# FPGA_R.net
KiCad netlist of a schematic drawn in Altium Designer
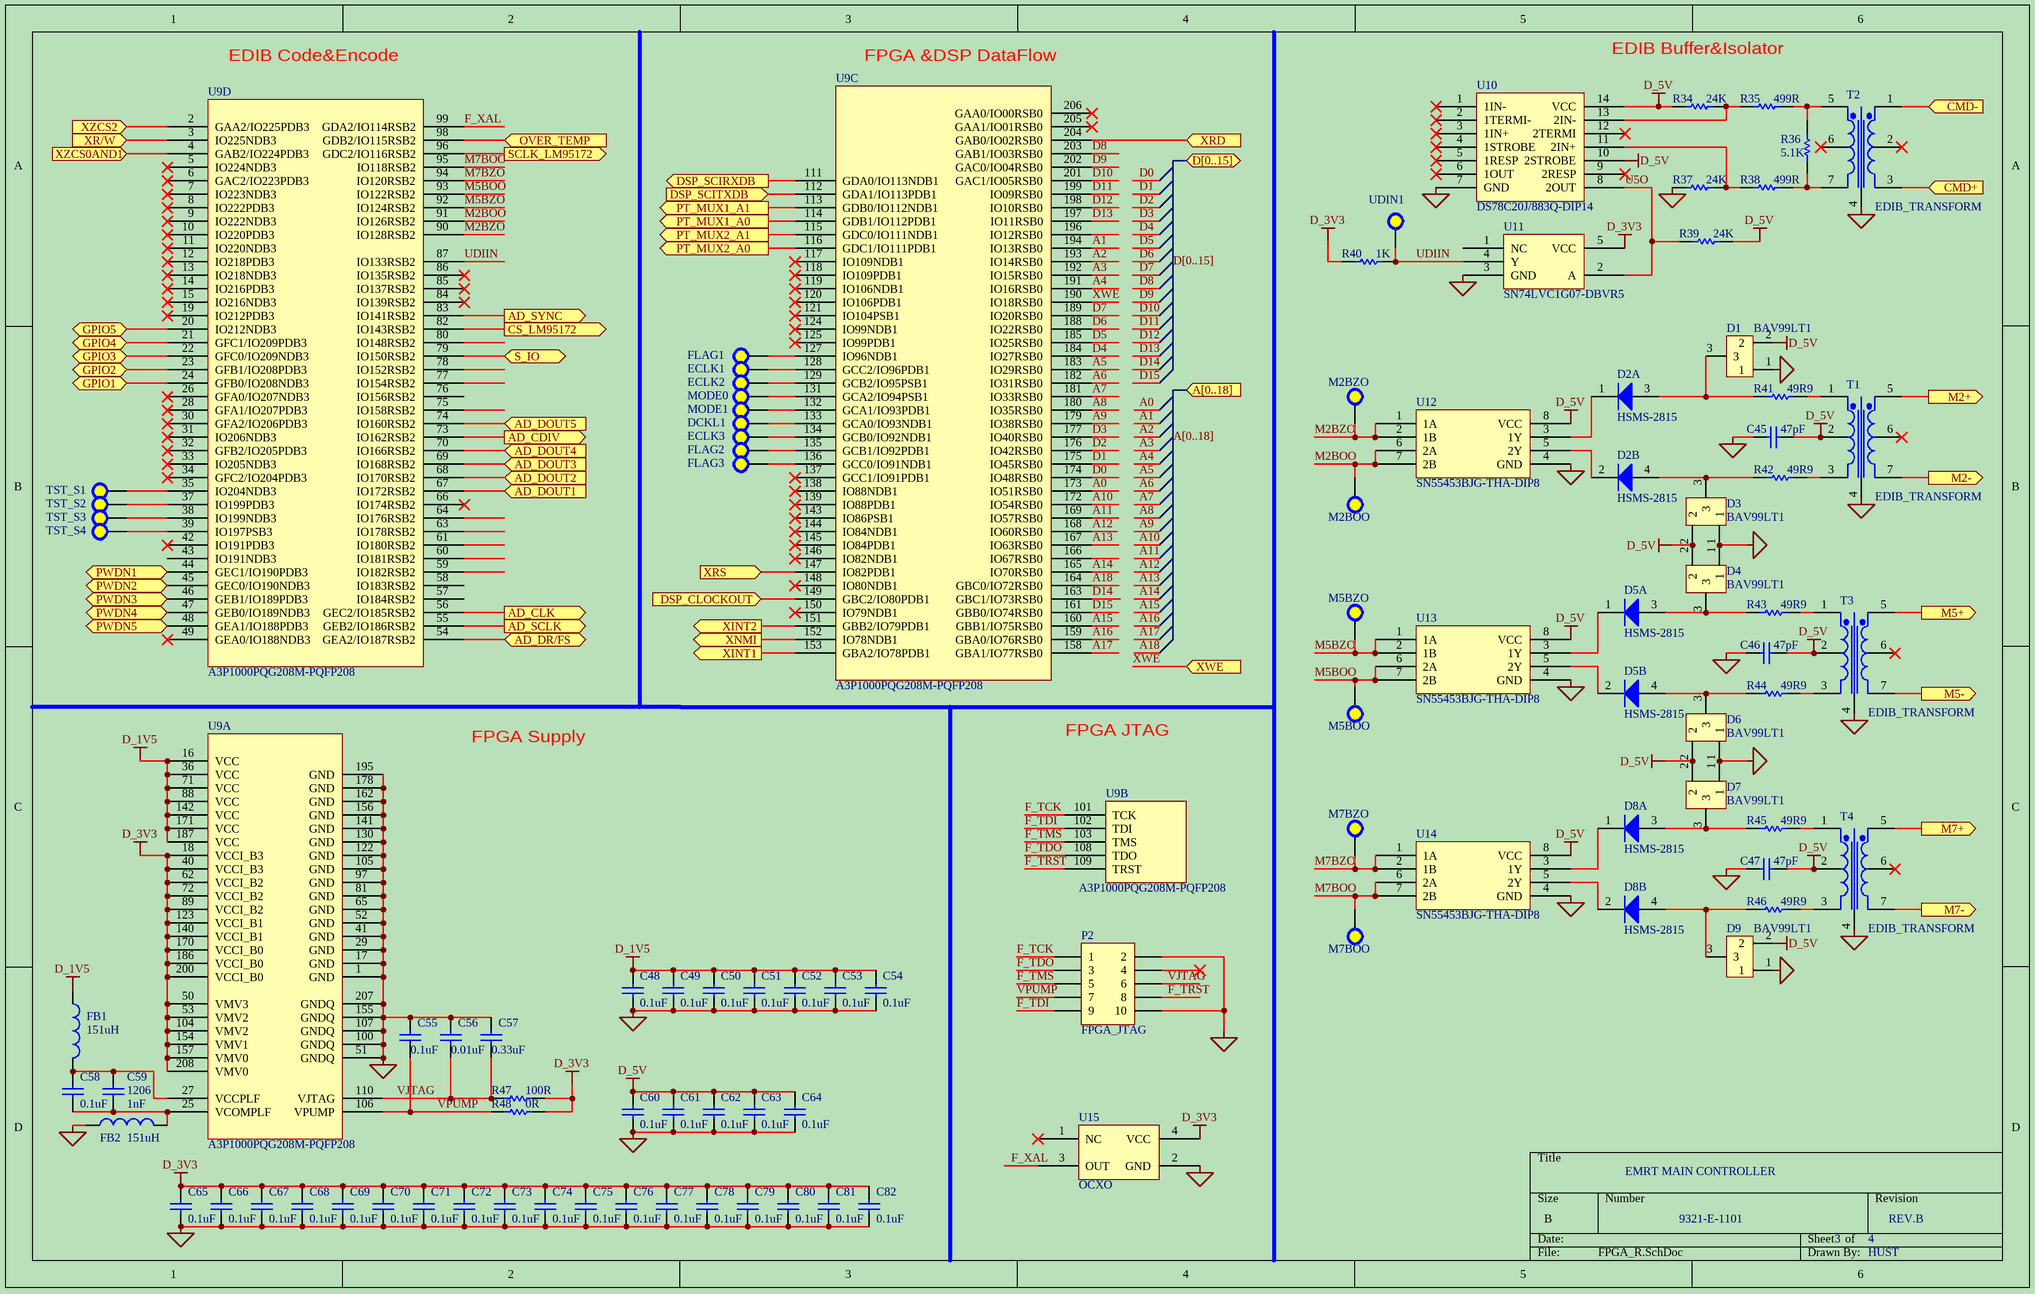
[diagram p0: FPGA_R.SchDoc]

(export (version "E")
  (design (tool "Eeschema 10.0.6"))
  (components
    (comp (ref "C45")
      (value "47pF")
      (footprint "CAPS0805_57")
      (description "Capacitor")
      (fields (field (name "PART NUMBER") "Y20025084") (field (name "Comment") "Cap"))
      (libsource (lib "Cap") (part "Cap"))
    )
    (comp (ref "C46")
      (value "47pF")
      (footprint "CAPS0805_57")
      (description "Capacitor")
      (fields (field (name "PART NUMBER") "Y20025084") (field (name "Comment") "Cap"))
      (libsource (lib "Cap") (part "Cap"))
    )
    (comp (ref "C47")
      (value "47pF")
      (footprint "CAPS0805_57")
      (description "Capacitor")
      (fields (field (name "PART NUMBER") "Y20025084") (field (name "Comment") "Cap"))
      (libsource (lib "Cap") (part "Cap"))
    )
    (comp (ref "C48")
      (value "0.1uF")
      (footprint "CAPS0805_57")
      (description "Capacitor")
      (fields (field (name "PART NUMBER") "Y20025084") (field (name "Comment") "Cap"))
      (libsource (lib "Cap") (part "Cap"))
    )
    (comp (ref "C49")
      (value "0.1uF")
      (footprint "CAPS0805_57")
      (description "Capacitor")
      (fields (field (name "PART NUMBER") "Y20025084") (field (name "Comment") "Cap"))
      (libsource (lib "Cap") (part "Cap"))
    )
    (comp (ref "C50")
      (value "0.1uF")
      (footprint "CAPS0805_57")
      (description "Capacitor")
      (fields (field (name "PART NUMBER") "Y20025084") (field (name "Comment") "Cap"))
      (libsource (lib "Cap") (part "Cap"))
    )
    (comp (ref "C51")
      (value "0.1uF")
      (footprint "CAPS0805_57")
      (description "Capacitor")
      (fields (field (name "PART NUMBER") "Y20025084") (field (name "Comment") "Cap"))
      (libsource (lib "Cap") (part "Cap"))
    )
    (comp (ref "C52")
      (value "0.1uF")
      (footprint "CAPS0805_57")
      (description "Capacitor")
      (fields (field (name "PART NUMBER") "Y20025084") (field (name "Comment") "Cap"))
      (libsource (lib "Cap") (part "Cap"))
    )
    (comp (ref "C53")
      (value "0.1uF")
      (footprint "CAPS0805_57")
      (description "Capacitor")
      (fields (field (name "PART NUMBER") "Y20025084") (field (name "Comment") "Cap"))
      (libsource (lib "Cap") (part "Cap"))
    )
    (comp (ref "C54")
      (value "0.1uF")
      (footprint "CAPS0805_57")
      (description "Capacitor")
      (fields (field (name "PART NUMBER") "Y20025084") (field (name "Comment") "Cap"))
      (libsource (lib "Cap") (part "Cap"))
    )
    (comp (ref "C55")
      (value "0.1uF")
      (footprint "CAPS0805_57")
      (description "Capacitor")
      (fields (field (name "PART NUMBER") "Y20025084") (field (name "Comment") "Cap"))
      (libsource (lib "Cap") (part "Cap"))
    )
    (comp (ref "C56")
      (value "0.01uF")
      (footprint "CAPS0805_57")
      (description "Capacitor")
      (fields (field (name "PART NUMBER") "Y20025084") (field (name "Comment") "Cap"))
      (libsource (lib "Cap") (part "Cap"))
    )
    (comp (ref "C57")
      (value "0.33uF")
      (footprint "CAPS0805_57")
      (description "Capacitor")
      (fields (field (name "PART NUMBER") "Y20025084") (field (name "Comment") "Cap"))
      (libsource (lib "Cap") (part "Cap"))
    )
    (comp (ref "C58")
      (value "0.1uF")
      (footprint "CAPS0805_57")
      (description "Capacitor")
      (fields (field (name "PART NUMBER") "Y20025084") (field (name "Comment") "Cap"))
      (libsource (lib "Cap") (part "Cap"))
    )
    (comp (ref "C59")
      (value "1206")
      (footprint "CAPS1206_43")
      (description "Capacitor")
      (fields (field (name "ALTIUM_VALUE") "1nF") (field (name "PART NUMBER") "Y20024113"))
      (libsource (lib "Cap") (part "Cap"))
    )
    (comp (ref "C60")
      (value "0.1uF")
      (footprint "CAPS0805_57")
      (description "Capacitor")
      (fields (field (name "PART NUMBER") "Y20025084") (field (name "Comment") "Cap"))
      (libsource (lib "Cap") (part "Cap"))
    )
    (comp (ref "C61")
      (value "0.1uF")
      (footprint "CAPS0805_57")
      (description "Capacitor")
      (fields (field (name "PART NUMBER") "Y20025084") (field (name "Comment") "Cap"))
      (libsource (lib "Cap") (part "Cap"))
    )
    (comp (ref "C62")
      (value "0.1uF")
      (footprint "CAPS0805_57")
      (description "Capacitor")
      (fields (field (name "PART NUMBER") "Y20025084") (field (name "Comment") "Cap"))
      (libsource (lib "Cap") (part "Cap"))
    )
    (comp (ref "C63")
      (value "0.1uF")
      (footprint "CAPS0805_57")
      (description "Capacitor")
      (fields (field (name "PART NUMBER") "Y20025084") (field (name "Comment") "Cap"))
      (libsource (lib "Cap") (part "Cap"))
    )
    (comp (ref "C64")
      (value "0.1uF")
      (footprint "CAPS0805_57")
      (description "Capacitor")
      (fields (field (name "PART NUMBER") "Y20025084") (field (name "Comment") "Cap"))
      (libsource (lib "Cap") (part "Cap"))
    )
    (comp (ref "C65")
      (value "0.1uF")
      (footprint "CAPS0805_57")
      (description "Capacitor")
      (fields (field (name "PART NUMBER") "Y20025084") (field (name "Comment") "Cap"))
      (libsource (lib "Cap") (part "Cap"))
    )
    (comp (ref "C66")
      (value "0.1uF")
      (footprint "CAPS0805_57")
      (description "Capacitor")
      (fields (field (name "PART NUMBER") "Y20025084") (field (name "Comment") "Cap"))
      (libsource (lib "Cap") (part "Cap"))
    )
    (comp (ref "C67")
      (value "0.1uF")
      (footprint "CAPS0805_57")
      (description "Capacitor")
      (fields (field (name "PART NUMBER") "Y20025084") (field (name "Comment") "Cap"))
      (libsource (lib "Cap") (part "Cap"))
    )
    (comp (ref "C68")
      (value "0.1uF")
      (footprint "CAPS0805_57")
      (description "Capacitor")
      (fields (field (name "PART NUMBER") "Y20025084") (field (name "Comment") "Cap"))
      (libsource (lib "Cap") (part "Cap"))
    )
    (comp (ref "C69")
      (value "0.1uF")
      (footprint "CAPS0805_57")
      (description "Capacitor")
      (fields (field (name "PART NUMBER") "Y20025084") (field (name "Comment") "Cap"))
      (libsource (lib "Cap") (part "Cap"))
    )
    (comp (ref "C70")
      (value "0.1uF")
      (footprint "CAPS0805_57")
      (description "Capacitor")
      (fields (field (name "PART NUMBER") "Y20025084") (field (name "Comment") "Cap"))
      (libsource (lib "Cap") (part "Cap"))
    )
    (comp (ref "C71")
      (value "0.1uF")
      (footprint "CAPS0805_57")
      (description "Capacitor")
      (fields (field (name "PART NUMBER") "Y20025084") (field (name "Comment") "Cap"))
      (libsource (lib "Cap") (part "Cap"))
    )
    (comp (ref "C72")
      (value "0.1uF")
      (footprint "CAPS0805_57")
      (description "Capacitor")
      (fields (field (name "PART NUMBER") "Y20025084") (field (name "Comment") "Cap"))
      (libsource (lib "Cap") (part "Cap"))
    )
    (comp (ref "C73")
      (value "0.1uF")
      (footprint "CAPS0805_57")
      (description "Capacitor")
      (fields (field (name "PART NUMBER") "Y20025084") (field (name "Comment") "Cap"))
      (libsource (lib "Cap") (part "Cap"))
    )
    (comp (ref "C74")
      (value "0.1uF")
      (footprint "CAPS0805_57")
      (description "Capacitor")
      (fields (field (name "PART NUMBER") "Y20025084") (field (name "Comment") "Cap"))
      (libsource (lib "Cap") (part "Cap"))
    )
    (comp (ref "C75")
      (value "0.1uF")
      (footprint "CAPS0805_57")
      (description "Capacitor")
      (fields (field (name "PART NUMBER") "Y20025084") (field (name "Comment") "Cap"))
      (libsource (lib "Cap") (part "Cap"))
    )
    (comp (ref "C76")
      (value "0.1uF")
      (footprint "CAPS0805_57")
      (description "Capacitor")
      (fields (field (name "PART NUMBER") "Y20025084") (field (name "Comment") "Cap"))
      (libsource (lib "Cap") (part "Cap"))
    )
    (comp (ref "C77")
      (value "0.1uF")
      (footprint "CAPS0805_57")
      (description "Capacitor")
      (fields (field (name "PART NUMBER") "Y20025084") (field (name "Comment") "Cap"))
      (libsource (lib "Cap") (part "Cap"))
    )
    (comp (ref "C78")
      (value "0.1uF")
      (footprint "CAPS0805_57")
      (description "Capacitor")
      (fields (field (name "PART NUMBER") "Y20025084") (field (name "Comment") "Cap"))
      (libsource (lib "Cap") (part "Cap"))
    )
    (comp (ref "C79")
      (value "0.1uF")
      (footprint "CAPS0805_57")
      (description "Capacitor")
      (fields (field (name "PART NUMBER") "Y20025084") (field (name "Comment") "Cap"))
      (libsource (lib "Cap") (part "Cap"))
    )
    (comp (ref "C80")
      (value "0.1uF")
      (footprint "CAPS0805_57")
      (description "Capacitor")
      (fields (field (name "PART NUMBER") "Y20025084") (field (name "Comment") "Cap"))
      (libsource (lib "Cap") (part "Cap"))
    )
    (comp (ref "C81")
      (value "0.1uF")
      (footprint "CAPS0805_57")
      (description "Capacitor")
      (fields (field (name "PART NUMBER") "Y20025084") (field (name "Comment") "Cap"))
      (libsource (lib "Cap") (part "Cap"))
    )
    (comp (ref "C82")
      (value "0.1uF")
      (footprint "CAPS0805_57")
      (description "Capacitor")
      (fields (field (name "PART NUMBER") "Y20025084") (field (name "Comment") "Cap"))
      (libsource (lib "Cap") (part "Cap"))
    )
    (comp (ref "D1")
      (value "BAV99LT1")
      (footprint "T-PDSO_3q290×240×111_p95")
      (libsource (lib "") (part "BAV99LT1_1"))
    )
    (comp (ref "D2")
      (value "HSMS-2815")
      (footprint "T-PDSO_4q290×240×110_p190")
      (libsource (lib "srj") (part "HSMS-2815"))
    )
    (comp (ref "D3")
      (value "BAV99LT1")
      (footprint "T-PDSO_3q290×240×111_p95")
      (libsource (lib "") (part "BAV99LT1_2"))
    )
    (comp (ref "D4")
      (value "BAV99LT1")
      (footprint "T-PDSO_3q290×240×111_p95")
      (libsource (lib "srj") (part "BAV99LT1"))
    )
    (comp (ref "D5")
      (value "HSMS-2815")
      (footprint "T-PDSO_4q290×240×110_p190")
      (libsource (lib "srj") (part "HSMS-2815"))
    )
    (comp (ref "D6")
      (value "BAV99LT1")
      (footprint "T-PDSO_3q290×240×111_p95")
      (libsource (lib "") (part "BAV99LT1_2"))
    )
    (comp (ref "D7")
      (value "BAV99LT1")
      (footprint "T-PDSO_3q290×240×111_p95")
      (libsource (lib "srj") (part "BAV99LT1"))
    )
    (comp (ref "D8")
      (value "HSMS-2815")
      (footprint "T-PDSO_4q290×240×110_p190")
      (libsource (lib "srj") (part "HSMS-2815"))
    )
    (comp (ref "D9")
      (value "BAV99LT1")
      (footprint "T-PDSO_3q290×240×111_p95")
      (libsource (lib "") (part "BAV99LT1_1"))
    )
    (comp (ref "DCKL1")
      (value "TEST_SMALL")
      (footprint "test_small")
      (libsource (lib "srj") (part "TEST_SMALL"))
    )
    (comp (ref "ECLK1")
      (value "TEST_SMALL")
      (footprint "test_small")
      (libsource (lib "srj") (part "TEST_SMALL"))
    )
    (comp (ref "ECLK2")
      (value "TEST_SMALL")
      (footprint "test_small")
      (libsource (lib "srj") (part "TEST_SMALL"))
    )
    (comp (ref "ECLK3")
      (value "TEST_SMALL")
      (footprint "test_small")
      (libsource (lib "srj") (part "TEST_SMALL"))
    )
    (comp (ref "FB1")
      (value "151uH")
      (footprint "inductor_1008")
      (description "Inductor")
      (fields
        (field (name "MANUFACTURER") "Generic Components")
        (field (name "PUBLISHER") "Altium Hobart Technology Centre")
      )
      (libsource (lib "Miscellaneous Devices") (part "Inductor"))
    )
    (comp (ref "FB2")
      (value "151uH")
      (footprint "inductor_1008")
      (description "Inductor")
      (fields
        (field (name "MANUFACTURER") "Generic Components")
        (field (name "PUBLISHER") "Altium Hobart Technology Centre")
      )
      (libsource (lib "Miscellaneous Devices") (part "Inductor"))
    )
    (comp (ref "FLAG1")
      (value "TEST_SMALL")
      (footprint "test_small")
      (libsource (lib "srj") (part "TEST_SMALL"))
    )
    (comp (ref "FLAG2")
      (value "TEST_SMALL")
      (footprint "test_small")
      (libsource (lib "srj") (part "TEST_SMALL"))
    )
    (comp (ref "FLAG3")
      (value "TEST_SMALL")
      (footprint "test_small")
      (libsource (lib "srj") (part "TEST_SMALL"))
    )
    (comp (ref "M2BOO")
      (value "TEST_SMALL")
      (footprint "test_small")
      (libsource (lib "srj") (part "TEST_SMALL"))
    )
    (comp (ref "M2BZO")
      (value "TEST_SMALL")
      (footprint "test_small")
      (libsource (lib "srj") (part "TEST_SMALL"))
    )
    (comp (ref "M5BOO")
      (value "TEST_SMALL")
      (footprint "test_small")
      (libsource (lib "srj") (part "TEST_SMALL"))
    )
    (comp (ref "M5BZO")
      (value "TEST_SMALL")
      (footprint "test_small")
      (libsource (lib "srj") (part "TEST_SMALL"))
    )
    (comp (ref "M7BOO")
      (value "TEST_SMALL")
      (footprint "test_small")
      (libsource (lib "srj") (part "TEST_SMALL"))
    )
    (comp (ref "M7BZO")
      (value "TEST_SMALL")
      (footprint "test_small")
      (libsource (lib "srj") (part "TEST_SMALL"))
    )
    (comp (ref "MODE0")
      (value "TEST_SMALL")
      (footprint "test_small")
      (libsource (lib "srj") (part "TEST_SMALL"))
    )
    (comp (ref "MODE1")
      (value "TEST_SMALL")
      (footprint "test_small")
      (libsource (lib "srj") (part "TEST_SMALL"))
    )
    (comp (ref "P2")
      (value "FPGA_JTAG")
      (footprint "HDR2X5")
      (description "Header, 5-Pin, Dual row")
      (fields (field (name "PUBLISHER") "Altium Limited"))
      (libsource (lib "Miscellaneous Connectors") (part "Header 5X2"))
    )
    (comp (ref "R34")
      (value "24K")
      (footprint "RESS0805")
      (description "Semiconductor Resistor")
      (fields
        (field (name "MANUFACTURER") "Generic Components")
        (field (name "Comment") "Res")
        (field (name "PUBLISHER") "Altium Hobart Technology Centre")
      )
      (libsource (lib "EMRT MAIN CONTROLLER") (part "Res"))
    )
    (comp (ref "R35")
      (value "499R")
      (footprint "RESS0805")
      (description "Semiconductor Resistor")
      (fields
        (field (name "MANUFACTURER") "Generic Components")
        (field (name "Comment") "Res")
        (field (name "PUBLISHER") "Altium Hobart Technology Centre")
      )
      (libsource (lib "EMRT MAIN CONTROLLER") (part "Res"))
    )
    (comp (ref "R36")
      (value "5.1K")
      (footprint "RESS0805")
      (description "Semiconductor Resistor")
      (fields
        (field (name "MANUFACTURER") "Generic Components")
        (field (name "Comment") "Res")
        (field (name "PUBLISHER") "Altium Hobart Technology Centre")
      )
      (libsource (lib "EMRT MAIN CONTROLLER") (part "Res"))
    )
    (comp (ref "R37")
      (value "24K")
      (footprint "RESS0805")
      (description "Semiconductor Resistor")
      (fields
        (field (name "MANUFACTURER") "Generic Components")
        (field (name "Comment") "Res")
        (field (name "PUBLISHER") "Altium Hobart Technology Centre")
      )
      (libsource (lib "EMRT MAIN CONTROLLER") (part "Res"))
    )
    (comp (ref "R38")
      (value "499R")
      (footprint "RESS0805")
      (description "Semiconductor Resistor")
      (fields
        (field (name "MANUFACTURER") "Generic Components")
        (field (name "Comment") "Res")
        (field (name "PUBLISHER") "Altium Hobart Technology Centre")
      )
      (libsource (lib "EMRT MAIN CONTROLLER") (part "Res"))
    )
    (comp (ref "R39")
      (value "24K")
      (footprint "RESS0805")
      (description "Semiconductor Resistor")
      (fields
        (field (name "MANUFACTURER") "Generic Components")
        (field (name "Comment") "Res")
        (field (name "PUBLISHER") "Altium Hobart Technology Centre")
      )
      (libsource (lib "EMRT MAIN CONTROLLER") (part "Res"))
    )
    (comp (ref "R40")
      (value "1K")
      (footprint "RESS0805")
      (description "Semiconductor Resistor")
      (fields
        (field (name "MANUFACTURER") "Generic Components")
        (field (name "Comment") "Res")
        (field (name "PUBLISHER") "Altium Hobart Technology Centre")
      )
      (libsource (lib "EMRT MAIN CONTROLLER") (part "Res"))
    )
    (comp (ref "R41")
      (value "49R9")
      (footprint "RESS0805")
      (description "Semiconductor Resistor")
      (fields
        (field (name "MANUFACTURER") "Generic Components")
        (field (name "Comment") "Res")
        (field (name "PUBLISHER") "Altium Hobart Technology Centre")
      )
      (libsource (lib "EMRT MAIN CONTROLLER") (part "Res"))
    )
    (comp (ref "R42")
      (value "49R9")
      (footprint "RESS0805")
      (description "Semiconductor Resistor")
      (fields
        (field (name "MANUFACTURER") "Generic Components")
        (field (name "Comment") "Res")
        (field (name "PUBLISHER") "Altium Hobart Technology Centre")
      )
      (libsource (lib "EMRT MAIN CONTROLLER") (part "Res"))
    )
    (comp (ref "R43")
      (value "49R9")
      (footprint "RESS0805")
      (description "Semiconductor Resistor")
      (fields
        (field (name "MANUFACTURER") "Generic Components")
        (field (name "Comment") "Res")
        (field (name "PUBLISHER") "Altium Hobart Technology Centre")
      )
      (libsource (lib "EMRT MAIN CONTROLLER") (part "Res"))
    )
    (comp (ref "R44")
      (value "49R9")
      (footprint "RESS0805")
      (description "Semiconductor Resistor")
      (fields
        (field (name "MANUFACTURER") "Generic Components")
        (field (name "Comment") "Res")
        (field (name "PUBLISHER") "Altium Hobart Technology Centre")
      )
      (libsource (lib "EMRT MAIN CONTROLLER") (part "Res"))
    )
    (comp (ref "R45")
      (value "49R9")
      (footprint "RESS0805")
      (description "Semiconductor Resistor")
      (fields
        (field (name "MANUFACTURER") "Generic Components")
        (field (name "Comment") "Res")
        (field (name "PUBLISHER") "Altium Hobart Technology Centre")
      )
      (libsource (lib "EMRT MAIN CONTROLLER") (part "Res"))
    )
    (comp (ref "R46")
      (value "49R9")
      (footprint "RESS0805")
      (description "Semiconductor Resistor")
      (fields
        (field (name "MANUFACTURER") "Generic Components")
        (field (name "Comment") "Res")
        (field (name "PUBLISHER") "Altium Hobart Technology Centre")
      )
      (libsource (lib "EMRT MAIN CONTROLLER") (part "Res"))
    )
    (comp (ref "R47")
      (value "100R")
      (footprint "RESS0805")
      (description "Semiconductor Resistor")
      (fields
        (field (name "MANUFACTURER") "Generic Components")
        (field (name "Comment") "Res")
        (field (name "PUBLISHER") "Altium Hobart Technology Centre")
      )
      (libsource (lib "EMRT MAIN CONTROLLER") (part "Res"))
    )
    (comp (ref "R48")
      (value "0R")
      (footprint "RESS0805")
      (description "Semiconductor Resistor")
      (fields
        (field (name "MANUFACTURER") "Generic Components")
        (field (name "Comment") "Res")
        (field (name "PUBLISHER") "Altium Hobart Technology Centre")
      )
      (libsource (lib "EMRT MAIN CONTROLLER") (part "Res"))
    )
    (comp (ref "T1")
      (value "EDIB_TRANSFORM")
      (footprint "TRANSFORM")
      (libsource (lib "srj") (part "EDIB_TRANSFORM"))
    )
    (comp (ref "T2")
      (value "EDIB_TRANSFORM")
      (footprint "TRANSFORM")
      (libsource (lib "") (part "EDIB_TRANSFORM_1"))
    )
    (comp (ref "T3")
      (value "EDIB_TRANSFORM")
      (footprint "TRANSFORM")
      (libsource (lib "srj") (part "EDIB_TRANSFORM"))
    )
    (comp (ref "T4")
      (value "EDIB_TRANSFORM")
      (footprint "TRANSFORM")
      (libsource (lib "srj") (part "EDIB_TRANSFORM"))
    )
    (comp (ref "TST_S1")
      (value "TEST_SMALL")
      (footprint "test_small")
      (libsource (lib "srj") (part "TEST_SMALL"))
    )
    (comp (ref "TST_S2")
      (value "TEST_SMALL")
      (footprint "test_small")
      (libsource (lib "srj") (part "TEST_SMALL"))
    )
    (comp (ref "TST_S3")
      (value "TEST_SMALL")
      (footprint "test_small")
      (libsource (lib "srj") (part "TEST_SMALL"))
    )
    (comp (ref "TST_S4")
      (value "TEST_SMALL")
      (footprint "test_small")
      (libsource (lib "srj") (part "TEST_SMALL"))
    )
    (comp (ref "U9")
      (value "A3P1000PQG208M-PQFP208")
      (footprint "PQFP208")
      (libsource (lib "srj") (part "A3P1000"))
    )
    (comp (ref "U10")
      (value "DS78C20J/883Q-DIP14")
      (footprint "CDIP_14q785×305×200_d18_p100_i300")
      (libsource (lib "srj") (part "DS78C20"))
    )
    (comp (ref "U11")
      (value "SN74LVC1G07-DBVR5")
      (footprint "PDSO_5q290×280×145_p95")
      (description "SN74LVC1G07")
      (libsource (lib "srj") (part "SN74LVC1G07"))
    )
    (comp (ref "U12")
      (value "SN55453BJG-THA-DIP8")
      (footprint "CDIP_8q405×305×200_d19_p100_i300")
      (libsource (lib "srj") (part "SN75453BD"))
    )
    (comp (ref "U13")
      (value "SN55453BJG-THA-DIP8")
      (footprint "CDIP_8q405×305×200_d19_p100_i300")
      (libsource (lib "srj") (part "SN75453BD"))
    )
    (comp (ref "U14")
      (value "SN55453BJG-THA-DIP8")
      (footprint "CDIP_8q405×305×200_d19_p100_i300")
      (libsource (lib "srj") (part "SN75453BD"))
    )
    (comp (ref "U15") (value "OCXO") (footprint "OCX1") (libsource (lib "srj") (part "OCXO")))
    (comp (ref "UDIN1")
      (value "TEST_SMALL")
      (footprint "test_small")
      (libsource (lib "srj") (part "TEST_SMALL"))
    )
  )
  (nets
    (net (code "1") (name "/A0") (class "Default")
      (node (ref "U9") (pin "173") (pinfunction "IO51RSB0_173") (pintype "passive"))
    )
    (net (code "2") (name "/A1") (class "Default")
      (node (ref "U9") (pin "194") (pinfunction "IO13RSB0_194") (pintype "passive"))
    )
    (net (code "3") (name "/A2") (class "Default")
      (node (ref "U9") (pin "193") (pinfunction "IO14RSB0_193") (pintype "passive"))
    )
    (net (code "4") (name "/A3") (class "Default")
      (node (ref "U9") (pin "192") (pinfunction "IO15RSB0_192") (pintype "passive"))
    )
    (net (code "5") (name "/A4") (class "Default")
      (node (ref "U9") (pin "191") (pinfunction "IO16RSB0_191") (pintype "passive"))
    )
    (net (code "6") (name "/A5") (class "Default")
      (node (ref "U9") (pin "183") (pinfunction "IO29RSB0_183") (pintype "passive"))
    )
    (net (code "7") (name "/A6") (class "Default")
      (node (ref "U9") (pin "182") (pinfunction "IO31RSB0_182") (pintype "passive"))
    )
    (net (code "8") (name "/A7") (class "Default")
      (node (ref "U9") (pin "181") (pinfunction "IO33RSB0_181") (pintype "passive"))
    )
    (net (code "9") (name "/A8") (class "Default")
      (node (ref "U9") (pin "180") (pinfunction "IO35RSB0_180") (pintype "passive"))
    )
    (net (code "10") (name "/A9") (class "Default")
      (node (ref "U9") (pin "179") (pinfunction "IO38RSB0_179") (pintype "passive"))
    )
    (net (code "11") (name "/A10") (class "Default")
      (node (ref "U9") (pin "172") (pinfunction "IO54RSB0_172") (pintype "passive"))
    )
    (net (code "12") (name "/A11") (class "Default")
      (node (ref "U9") (pin "169") (pinfunction "IO57RSB0_169") (pintype "passive"))
    )
    (net (code "13") (name "/A12") (class "Default")
      (node (ref "U9") (pin "168") (pinfunction "IO60RSB0_168") (pintype "passive"))
    )
    (net (code "14") (name "/A13") (class "Default")
      (node (ref "U9") (pin "167") (pinfunction "IO63RSB0_167") (pintype "passive"))
    )
    (net (code "15") (name "/A14") (class "Default")
      (node (ref "U9") (pin "165") (pinfunction "IO70RSB0_165") (pintype "passive"))
    )
    (net (code "16") (name "/A15") (class "Default")
      (node (ref "U9") (pin "160") (pinfunction "GBB1/IO75RSB0_160") (pintype "passive"))
    )
    (net (code "17") (name "/A16") (class "Default")
      (node (ref "U9") (pin "159") (pinfunction "GBA0/IO76RSB0_159") (pintype "passive"))
    )
    (net (code "18") (name "/A17") (class "Default")
      (node (ref "U9") (pin "158") (pinfunction "GBA1/IO77RSB0_158") (pintype "passive"))
    )
    (net (code "19") (name "/A18") (class "Default")
      (node (ref "U9") (pin "164") (pinfunction "GBC0/IO72RSB0_164") (pintype "passive"))
    )
    (net (code "20") (name "/AD_CDIV") (class "Default")
      (node (ref "U9") (pin "73") (pinfunction "IO162RSB2_73") (pintype "passive"))
    )
    (net (code "21") (name "/AD_CLK") (class "Default")
      (node (ref "U9") (pin "56") (pinfunction "GEC2/IO185RSB2_56") (pintype "passive"))
    )
    (net (code "22") (name "/AD_DOUT1") (class "Default")
      (node (ref "U9") (pin "67") (pinfunction "IO172RSB2_67") (pintype "passive"))
    )
    (net (code "23") (name "/AD_DOUT2") (class "Default")
      (node (ref "U9") (pin "68") (pinfunction "IO170RSB2_68") (pintype "passive"))
    )
    (net (code "24") (name "/AD_DOUT3") (class "Default")
      (node (ref "U9") (pin "69") (pinfunction "IO168RSB2_69") (pintype "passive"))
    )
    (net (code "25") (name "/AD_DOUT4") (class "Default")
      (node (ref "U9") (pin "70") (pinfunction "IO166RSB2_70") (pintype "passive"))
    )
    (net (code "26") (name "/AD_DOUT5") (class "Default")
      (node (ref "U9") (pin "74") (pinfunction "IO160RSB2_74") (pintype "passive"))
    )
    (net (code "27") (name "/AD_DR{slash}FS") (class "Default")
      (node (ref "U9") (pin "54") (pinfunction "GEA2/IO187RSB2_54") (pintype "passive"))
    )
    (net (code "28") (name "/AD_SCLK") (class "Default")
      (node (ref "U9") (pin "55") (pinfunction "GEB2/IO186RSB2_55") (pintype "passive"))
    )
    (net (code "29") (name "/AD_SYNC") (class "Default")
      (node (ref "U9") (pin "83") (pinfunction "IO141RSB2_83") (pintype "passive"))
    )
    (net (code "31") (name "/CMD+") (class "Default")
      (node (ref "T2") (pin "3") (pinfunction "Pri-_3") (pintype "passive"))
    )
    (net (code "32") (name "/CMD-") (class "Default")
      (node (ref "T2") (pin "1") (pinfunction "Pri+_1") (pintype "passive"))
    )
    (net (code "33") (name "/CS_LM95172") (class "Default")
      (node (ref "U9") (pin "82") (pinfunction "IO143RSB2_82") (pintype "passive"))
    )
    (net (code "34") (name "/D0") (class "Default")
      (node (ref "U9") (pin "174") (pinfunction "IO48RSB0_174") (pintype "passive"))
    )
    (net (code "35") (name "/D1") (class "Default")
      (node (ref "U9") (pin "175") (pinfunction "IO45RSB0_175") (pintype "passive"))
    )
    (net (code "36") (name "/D2") (class "Default")
      (node (ref "U9") (pin "176") (pinfunction "IO42RSB0_176") (pintype "passive"))
    )
    (net (code "37") (name "/D3") (class "Default")
      (node (ref "U9") (pin "177") (pinfunction "IO40RSB0_177") (pintype "passive"))
    )
    (net (code "38") (name "/D4") (class "Default")
      (node (ref "U9") (pin "184") (pinfunction "IO27RSB0_184") (pintype "passive"))
    )
    (net (code "39") (name "/D5") (class "Default")
      (node (ref "U9") (pin "185") (pinfunction "IO25RSB0_185") (pintype "passive"))
    )
    (net (code "40") (name "/D6") (class "Default")
      (node (ref "U9") (pin "188") (pinfunction "IO22RSB0_188") (pintype "passive"))
    )
    (net (code "41") (name "/D7") (class "Default")
      (node (ref "U9") (pin "189") (pinfunction "IO20RSB0_189") (pintype "passive"))
    )
    (net (code "42") (name "/D8") (class "Default")
      (node (ref "U9") (pin "203") (pinfunction "GAB1/IO03RSB0_203") (pintype "passive"))
    )
    (net (code "43") (name "/D9") (class "Default")
      (node (ref "U9") (pin "202") (pinfunction "GAC0/IO04RSB0_202") (pintype "passive"))
    )
    (net (code "44") (name "/D10") (class "Default")
      (node (ref "U9") (pin "201") (pinfunction "GAC1/IO05RSB0_201") (pintype "passive"))
    )
    (net (code "45") (name "/D11") (class "Default")
      (node (ref "U9") (pin "199") (pinfunction "IO09RSB0_199") (pintype "passive"))
    )
    (net (code "46") (name "/D12") (class "Default")
      (node (ref "U9") (pin "198") (pinfunction "IO10RSB0_198") (pintype "passive"))
    )
    (net (code "47") (name "/D13") (class "Default")
      (node (ref "U9") (pin "197") (pinfunction "IO11RSB0_197") (pintype "passive"))
    )
    (net (code "48") (name "/D14") (class "Default")
      (node (ref "U9") (pin "163") (pinfunction "GBC1/IO73RSB0_163") (pintype "passive"))
    )
    (net (code "49") (name "/D15") (class "Default")
      (node (ref "U9") (pin "161") (pinfunction "GBB0/IO74RSB0_161") (pintype "passive"))
    )
    (net (code "50") (name "/DSP_CLOCKOUT") (class "Default")
      (node (ref "U9") (pin "149") (pinfunction "GBC2/IO80PDB1_149") (pintype "passive"))
    )
    (net (code "51") (name "/DSP_SCIRXDB") (class "Default")
      (node (ref "U9") (pin "111") (pinfunction "GDA0/IO113NDB1_111") (pintype "passive"))
    )
    (net (code "52") (name "/DSP_SCITXDB") (class "Default")
      (node (ref "U9") (pin "112") (pinfunction "GDA1/IO113PDB1_112") (pintype "passive"))
    )
    (net (code "54") (name "/F_TCK") (class "Default")
      (node (ref "P2") (pin "1") (pinfunction "1_1") (pintype "passive"))
      (node (ref "U9") (pin "101") (pinfunction "TCK_101") (pintype "passive"))
    )
    (net (code "55") (name "/F_TDI") (class "Default")
      (node (ref "P2") (pin "9") (pinfunction "9_9") (pintype "passive"))
      (node (ref "U9") (pin "102") (pinfunction "TDI_102") (pintype "passive"))
    )
    (net (code "56") (name "/F_TDO") (class "Default")
      (node (ref "P2") (pin "3") (pinfunction "3_3") (pintype "passive"))
      (node (ref "U9") (pin "108") (pinfunction "TDO_108") (pintype "passive"))
    )
    (net (code "57") (name "/F_TMS") (class "Default")
      (node (ref "P2") (pin "5") (pinfunction "5_5") (pintype "passive"))
      (node (ref "U9") (pin "103") (pinfunction "TMS_103") (pintype "passive"))
    )
    (net (code "58") (name "/F_TRST") (class "Default")
      (node (ref "P2") (pin "8") (pinfunction "8_8") (pintype "passive"))
      (node (ref "U9") (pin "109") (pinfunction "TRST_109") (pintype "passive"))
    )
    (net (code "59") (name "/F_XAL") (class "Default")
      (node (ref "U15") (pin "3") (pinfunction "OUT_3") (pintype "passive"))
      (node (ref "U9") (pin "99") (pinfunction "GDA2/IO114RSB2_99") (pintype "passive"))
    )
    (net (code "60") (name "/GPIO1") (class "Default")
      (node (ref "U9") (pin "24") (pinfunction "GFB0/IO208NDB3_24") (pintype "passive"))
    )
    (net (code "61") (name "/GPIO2") (class "Default")
      (node (ref "U9") (pin "23") (pinfunction "GFB1/IO208PDB3_23") (pintype "passive"))
    )
    (net (code "62") (name "/GPIO3") (class "Default")
      (node (ref "U9") (pin "22") (pinfunction "GFC0/IO209NDB3_22") (pintype "passive"))
    )
    (net (code "63") (name "/GPIO4") (class "Default")
      (node (ref "U9") (pin "21") (pinfunction "GFC1/IO209PDB3_21") (pintype "passive"))
    )
    (net (code "64") (name "/GPIO5") (class "Default")
      (node (ref "U9") (pin "20") (pinfunction "IO212NDB3_20") (pintype "passive"))
    )
    (net (code "65") (name "/M2+") (class "Default")
      (node (ref "T1") (pin "5") (pinfunction "Sec-_5") (pintype "passive"))
    )
    (net (code "66") (name "/M2-") (class "Default")
      (node (ref "T1") (pin "7") (pinfunction "Sec+_7") (pintype "passive"))
    )
    (net (code "67") (name "/M2BOO") (class "Default")
      (node (ref "M2BOO") (pin "1") (pinfunction "1_1") (pintype "passive"))
      (node (ref "U12") (pin "6") (pinfunction "2A_6") (pintype "passive"))
      (node (ref "U12") (pin "7") (pinfunction "2B_7") (pintype "passive"))
      (node (ref "U9") (pin "91") (pinfunction "IO126RSB2_91") (pintype "passive"))
    )
    (net (code "68") (name "/M2BZO") (class "Default")
      (node (ref "M2BZO") (pin "1") (pinfunction "1_1") (pintype "passive"))
      (node (ref "U12") (pin "1") (pinfunction "1A_1") (pintype "passive"))
      (node (ref "U12") (pin "2") (pinfunction "1B_2") (pintype "passive"))
      (node (ref "U9") (pin "90") (pinfunction "IO128RSB2_90") (pintype "passive"))
    )
    (net (code "69") (name "/M5+") (class "Default")
      (node (ref "T3") (pin "5") (pinfunction "Sec-_5") (pintype "passive"))
    )
    (net (code "70") (name "/M5-") (class "Default")
      (node (ref "T3") (pin "7") (pinfunction "Sec+_7") (pintype "passive"))
    )
    (net (code "71") (name "/M5BOO") (class "Default")
      (node (ref "M5BOO") (pin "1") (pinfunction "1_1") (pintype "passive"))
      (node (ref "U13") (pin "6") (pinfunction "2A_6") (pintype "passive"))
      (node (ref "U13") (pin "7") (pinfunction "2B_7") (pintype "passive"))
      (node (ref "U9") (pin "93") (pinfunction "IO122RSB2_93") (pintype "passive"))
    )
    (net (code "72") (name "/M5BZO") (class "Default")
      (node (ref "M5BZO") (pin "1") (pinfunction "1_1") (pintype "passive"))
      (node (ref "U13") (pin "1") (pinfunction "1A_1") (pintype "passive"))
      (node (ref "U13") (pin "2") (pinfunction "1B_2") (pintype "passive"))
      (node (ref "U9") (pin "92") (pinfunction "IO124RSB2_92") (pintype "passive"))
    )
    (net (code "73") (name "/M7+") (class "Default")
      (node (ref "T4") (pin "5") (pinfunction "Sec-_5") (pintype "passive"))
    )
    (net (code "74") (name "/M7-") (class "Default")
      (node (ref "T4") (pin "7") (pinfunction "Sec+_7") (pintype "passive"))
    )
    (net (code "75") (name "/M7BOO") (class "Default")
      (node (ref "M7BOO") (pin "1") (pinfunction "1_1") (pintype "passive"))
      (node (ref "U14") (pin "6") (pinfunction "2A_6") (pintype "passive"))
      (node (ref "U14") (pin "7") (pinfunction "2B_7") (pintype "passive"))
      (node (ref "U9") (pin "95") (pinfunction "IO118RSB2_95") (pintype "passive"))
    )
    (net (code "76") (name "/M7BZO") (class "Default")
      (node (ref "M7BZO") (pin "1") (pinfunction "1_1") (pintype "passive"))
      (node (ref "U14") (pin "1") (pinfunction "1A_1") (pintype "passive"))
      (node (ref "U14") (pin "2") (pinfunction "1B_2") (pintype "passive"))
      (node (ref "U9") (pin "94") (pinfunction "IO120RSB2_94") (pintype "passive"))
    )
    (net (code "77") (name "/OVER_TEMP") (class "Default")
      (node (ref "U9") (pin "98") (pinfunction "GDB2/IO115RSB2_98") (pintype "passive"))
    )
    (net (code "78") (name "/PT_MUX1_A0") (class "Default")
      (node (ref "U9") (pin "114") (pinfunction "GDB1/IO112PDB1_114") (pintype "passive"))
    )
    (net (code "79") (name "/PT_MUX1_A1") (class "Default")
      (node (ref "U9") (pin "113") (pinfunction "GDB0/IO112NDB1_113") (pintype "passive"))
    )
    (net (code "80") (name "/PT_MUX2_A0") (class "Default")
      (node (ref "U9") (pin "116") (pinfunction "GDC1/IO111PDB1_116") (pintype "passive"))
    )
    (net (code "81") (name "/PT_MUX2_A1") (class "Default")
      (node (ref "U9") (pin "115") (pinfunction "GDC0/IO111NDB1_115") (pintype "passive"))
    )
    (net (code "82") (name "/PWDN1") (class "Default")
      (node (ref "U9") (pin "44") (pinfunction "GEC1/IO190PDB3_44") (pintype "passive"))
    )
    (net (code "83") (name "/PWDN2") (class "Default")
      (node (ref "U9") (pin "45") (pinfunction "GEC0/IO190NDB3_45") (pintype "passive"))
    )
    (net (code "84") (name "/PWDN3") (class "Default")
      (node (ref "U9") (pin "46") (pinfunction "GEB1/IO189PDB3_46") (pintype "passive"))
    )
    (net (code "85") (name "/PWDN4") (class "Default")
      (node (ref "U9") (pin "47") (pinfunction "GEB0/IO189NDB3_47") (pintype "passive"))
    )
    (net (code "86") (name "/PWDN5") (class "Default")
      (node (ref "U9") (pin "48") (pinfunction "GEA1/IO188PDB3_48") (pintype "passive"))
    )
    (net (code "87") (name "/SCLK_LM95172") (class "Default")
      (node (ref "U9") (pin "96") (pinfunction "GDC2/IO116RSB2_96") (pintype "passive"))
    )
    (net (code "88") (name "/S_IO") (class "Default")
      (node (ref "U9") (pin "79") (pinfunction "IO150RSB2_79") (pintype "passive"))
    )
    (net (code "89") (name "/U5O") (class "Default")
      (node (ref "R39") (pin "1") (pinfunction "1_1") (pintype "passive"))
      (node (ref "U10") (pin "8") (pinfunction "2OUT_8") (pintype "passive"))
      (node (ref "U11") (pin "2") (pinfunction "A_2") (pintype "passive"))
    )
    (net (code "90") (name "/UDIIN") (class "Default")
      (node (ref "R40") (pin "2") (pinfunction "2_2") (pintype "passive"))
      (node (ref "U11") (pin "4") (pinfunction "Y_4") (pintype "passive"))
      (node (ref "U9") (pin "87") (pinfunction "IO133RSB2_87") (pintype "passive"))
      (node (ref "UDIN1") (pin "1") (pinfunction "1_1") (pintype "passive"))
    )
    (net (code "91") (name "/VJTAG") (class "Default")
      (node (ref "C56") (pin "1") (pinfunction "1_1") (pintype "passive"))
      (node (ref "C57") (pin "1") (pinfunction "1_1") (pintype "passive"))
      (node (ref "P2") (pin "6") (pinfunction "6_6") (pintype "passive"))
      (node (ref "R47") (pin "1") (pinfunction "1_1") (pintype "passive"))
      (node (ref "U9") (pin "110") (pinfunction "VJTAG_110") (pintype "passive"))
    )
    (net (code "92") (name "/VPUMP") (class "Default")
      (node (ref "C55") (pin "1") (pinfunction "1_1") (pintype "passive"))
      (node (ref "P2") (pin "7") (pinfunction "7_7") (pintype "passive"))
      (node (ref "R48") (pin "1") (pinfunction "1_1") (pintype "passive"))
      (node (ref "U9") (pin "106") (pinfunction "VPUMP_106") (pintype "passive"))
    )
    (net (code "93") (name "/XINT1") (class "Default")
      (node (ref "U9") (pin "153") (pinfunction "GBA2/IO78PDB1_153") (pintype "passive"))
    )
    (net (code "94") (name "/XINT2") (class "Default")
      (node (ref "U9") (pin "151") (pinfunction "GBB2/IO79PDB1_151") (pintype "passive"))
    )
    (net (code "95") (name "/XNMI") (class "Default")
      (node (ref "U9") (pin "152") (pinfunction "IO78NDB1_152") (pintype "passive"))
    )
    (net (code "96") (name "/XRD") (class "Default")
      (node (ref "U9") (pin "204") (pinfunction "GAB0/IO02RSB0_204") (pintype "passive"))
    )
    (net (code "97") (name "/XRS") (class "Default")
      (node (ref "U9") (pin "147") (pinfunction "IO82PDB1_147") (pintype "passive"))
    )
    (net (code "98") (name "/XR{slash}W") (class "Default")
      (node (ref "U9") (pin "3") (pinfunction "IO225NDB3_3") (pintype "passive"))
    )
    (net (code "99") (name "/XWE") (class "Default")
      (node (ref "U9") (pin "190") (pinfunction "IO18RSB0_190") (pintype "passive"))
    )
    (net (code "100") (name "/XZCS0AND1") (class "Default")
      (node (ref "U9") (pin "4") (pinfunction "GAB2/IO224PDB3_4") (pintype "passive"))
    )
    (net (code "101") (name "/XZCS2") (class "Default")
      (node (ref "U9") (pin "2") (pinfunction "GAA2/IO225PDB3_2") (pintype "passive"))
    )
    (net (code "102") (name "DGND") (class "Default")
      (node (ref "C45") (pin "2") (pinfunction "2_2") (pintype "passive"))
      (node (ref "C46") (pin "2") (pinfunction "2_2") (pintype "passive"))
      (node (ref "C47") (pin "2") (pinfunction "2_2") (pintype "passive"))
      (node (ref "C48") (pin "1") (pinfunction "1_1") (pintype "passive"))
      (node (ref "C49") (pin "1") (pinfunction "1_1") (pintype "passive"))
      (node (ref "C50") (pin "1") (pinfunction "1_1") (pintype "passive"))
      (node (ref "C51") (pin "1") (pinfunction "1_1") (pintype "passive"))
      (node (ref "C52") (pin "1") (pinfunction "1_1") (pintype "passive"))
      (node (ref "C53") (pin "1") (pinfunction "1_1") (pintype "passive"))
      (node (ref "C54") (pin "1") (pinfunction "1_1") (pintype "passive"))
      (node (ref "C55") (pin "2") (pinfunction "2_2") (pintype "passive"))
      (node (ref "C56") (pin "2") (pinfunction "2_2") (pintype "passive"))
      (node (ref "C57") (pin "2") (pinfunction "2_2") (pintype "passive"))
      (node (ref "C60") (pin "1") (pinfunction "1_1") (pintype "passive"))
      (node (ref "C61") (pin "1") (pinfunction "1_1") (pintype "passive"))
      (node (ref "C62") (pin "1") (pinfunction "1_1") (pintype "passive"))
      (node (ref "C63") (pin "1") (pinfunction "1_1") (pintype "passive"))
      (node (ref "C64") (pin "1") (pinfunction "1_1") (pintype "passive"))
      (node (ref "C65") (pin "1") (pinfunction "1_1") (pintype "passive"))
      (node (ref "C66") (pin "1") (pinfunction "1_1") (pintype "passive"))
      (node (ref "C67") (pin "1") (pinfunction "1_1") (pintype "passive"))
      (node (ref "C68") (pin "1") (pinfunction "1_1") (pintype "passive"))
      (node (ref "C69") (pin "1") (pinfunction "1_1") (pintype "passive"))
      (node (ref "C70") (pin "1") (pinfunction "1_1") (pintype "passive"))
      (node (ref "C71") (pin "1") (pinfunction "1_1") (pintype "passive"))
      (node (ref "C72") (pin "1") (pinfunction "1_1") (pintype "passive"))
      (node (ref "C73") (pin "1") (pinfunction "1_1") (pintype "passive"))
      (node (ref "C74") (pin "1") (pinfunction "1_1") (pintype "passive"))
      (node (ref "C75") (pin "1") (pinfunction "1_1") (pintype "passive"))
      (node (ref "C76") (pin "1") (pinfunction "1_1") (pintype "passive"))
      (node (ref "C77") (pin "1") (pinfunction "1_1") (pintype "passive"))
      (node (ref "C78") (pin "1") (pinfunction "1_1") (pintype "passive"))
      (node (ref "C79") (pin "1") (pinfunction "1_1") (pintype "passive"))
      (node (ref "C80") (pin "1") (pinfunction "1_1") (pintype "passive"))
      (node (ref "C81") (pin "1") (pinfunction "1_1") (pintype "passive"))
      (node (ref "C82") (pin "1") (pinfunction "1_1") (pintype "passive"))
      (node (ref "D1") (pin "1") (pinfunction "1_1") (pintype "passive"))
      (node (ref "D3") (pin "1") (pinfunction "1_1") (pintype "passive"))
      (node (ref "D4") (pin "1") (pinfunction "1_1") (pintype "passive"))
      (node (ref "D6") (pin "1") (pinfunction "1_1") (pintype "passive"))
      (node (ref "D7") (pin "1") (pinfunction "1_1") (pintype "passive"))
      (node (ref "D9") (pin "1") (pinfunction "1_1") (pintype "passive"))
      (node (ref "FB2") (pin "1") (pinfunction "1_1") (pintype "passive"))
      (node (ref "P2") (pin "10") (pinfunction "10_10") (pintype "passive"))
      (node (ref "P2") (pin "2") (pinfunction "2_2") (pintype "passive"))
      (node (ref "R37") (pin "1") (pinfunction "1_1") (pintype "passive"))
      (node (ref "T1") (pin "4") (pintype "passive"))
      (node (ref "T2") (pin "4") (pintype "passive"))
      (node (ref "T3") (pin "4") (pintype "passive"))
      (node (ref "T4") (pin "4") (pintype "passive"))
      (node (ref "U10") (pin "7") (pinfunction "GND_7") (pintype "passive"))
      (node (ref "U11") (pin "3") (pinfunction "GND_3") (pintype "passive"))
      (node (ref "U12") (pin "4") (pinfunction "GND_4") (pintype "passive"))
      (node (ref "U13") (pin "4") (pinfunction "GND_4") (pintype "passive"))
      (node (ref "U14") (pin "4") (pinfunction "GND_4") (pintype "passive"))
      (node (ref "U15") (pin "2") (pinfunction "GND_2") (pintype "passive"))
      (node (ref "U9") (pin "1") (pinfunction "GND_1") (pintype "passive"))
      (node (ref "U9") (pin "100") (pinfunction "GNDQ_100") (pintype "passive"))
      (node (ref "U9") (pin "105") (pinfunction "GND_105") (pintype "passive"))
      (node (ref "U9") (pin "107") (pinfunction "GNDQ_107") (pintype "passive"))
      (node (ref "U9") (pin "122") (pinfunction "GND_122") (pintype "passive"))
      (node (ref "U9") (pin "130") (pinfunction "GND_130") (pintype "passive"))
      (node (ref "U9") (pin "141") (pinfunction "GND_141") (pintype "passive"))
      (node (ref "U9") (pin "155") (pinfunction "GNDQ_155") (pintype "passive"))
      (node (ref "U9") (pin "156") (pinfunction "GND_156") (pintype "passive"))
      (node (ref "U9") (pin "162") (pinfunction "GND_162") (pintype "passive"))
      (node (ref "U9") (pin "17") (pinfunction "GND_17") (pintype "passive"))
      (node (ref "U9") (pin "178") (pinfunction "GND_178") (pintype "passive"))
      (node (ref "U9") (pin "195") (pinfunction "GND_195") (pintype "passive"))
      (node (ref "U9") (pin "207") (pinfunction "GNDQ_207") (pintype "passive"))
      (node (ref "U9") (pin "29") (pinfunction "GND_29") (pintype "passive"))
      (node (ref "U9") (pin "41") (pinfunction "GND_41") (pintype "passive"))
      (node (ref "U9") (pin "51") (pinfunction "GNDQ_51") (pintype "passive"))
      (node (ref "U9") (pin "52") (pinfunction "GND_52") (pintype "passive"))
      (node (ref "U9") (pin "65") (pinfunction "GND_65") (pintype "passive"))
      (node (ref "U9") (pin "81") (pinfunction "GND_81") (pintype "passive"))
      (node (ref "U9") (pin "97") (pinfunction "GND_97") (pintype "passive"))
    )
    (net (code "103") (name "D_1V5") (class "Default")
      (node (ref "C48") (pin "2") (pinfunction "2_2") (pintype "passive"))
      (node (ref "C49") (pin "2") (pinfunction "2_2") (pintype "passive"))
      (node (ref "C50") (pin "2") (pinfunction "2_2") (pintype "passive"))
      (node (ref "C51") (pin "2") (pinfunction "2_2") (pintype "passive"))
      (node (ref "C52") (pin "2") (pinfunction "2_2") (pintype "passive"))
      (node (ref "C53") (pin "2") (pinfunction "2_2") (pintype "passive"))
      (node (ref "C54") (pin "2") (pinfunction "2_2") (pintype "passive"))
      (node (ref "FB1") (pin "1") (pinfunction "1_1") (pintype "passive"))
      (node (ref "U9") (pin "142") (pinfunction "VCC_142") (pintype "passive"))
      (node (ref "U9") (pin "16") (pinfunction "VCC_16") (pintype "passive"))
      (node (ref "U9") (pin "171") (pinfunction "VCC_171") (pintype "passive"))
      (node (ref "U9") (pin "187") (pinfunction "VCC_187") (pintype "passive"))
      (node (ref "U9") (pin "36") (pinfunction "VCC_36") (pintype "passive"))
      (node (ref "U9") (pin "71") (pinfunction "VCC_71") (pintype "passive"))
      (node (ref "U9") (pin "88") (pinfunction "VCC_88") (pintype "passive"))
    )
    (net (code "104") (name "D_3V3") (class "Default")
      (node (ref "C65") (pin "2") (pinfunction "2_2") (pintype "passive"))
      (node (ref "C66") (pin "2") (pinfunction "2_2") (pintype "passive"))
      (node (ref "C67") (pin "2") (pinfunction "2_2") (pintype "passive"))
      (node (ref "C68") (pin "2") (pinfunction "2_2") (pintype "passive"))
      (node (ref "C69") (pin "2") (pinfunction "2_2") (pintype "passive"))
      (node (ref "C70") (pin "2") (pinfunction "2_2") (pintype "passive"))
      (node (ref "C71") (pin "2") (pinfunction "2_2") (pintype "passive"))
      (node (ref "C72") (pin "2") (pinfunction "2_2") (pintype "passive"))
      (node (ref "C73") (pin "2") (pinfunction "2_2") (pintype "passive"))
      (node (ref "C74") (pin "2") (pinfunction "2_2") (pintype "passive"))
      (node (ref "C75") (pin "2") (pinfunction "2_2") (pintype "passive"))
      (node (ref "C76") (pin "2") (pinfunction "2_2") (pintype "passive"))
      (node (ref "C77") (pin "2") (pinfunction "2_2") (pintype "passive"))
      (node (ref "C78") (pin "2") (pinfunction "2_2") (pintype "passive"))
      (node (ref "C79") (pin "2") (pinfunction "2_2") (pintype "passive"))
      (node (ref "C80") (pin "2") (pinfunction "2_2") (pintype "passive"))
      (node (ref "C81") (pin "2") (pinfunction "2_2") (pintype "passive"))
      (node (ref "C82") (pin "2") (pinfunction "2_2") (pintype "passive"))
      (node (ref "R40") (pin "1") (pinfunction "1_1") (pintype "passive"))
      (node (ref "R47") (pin "2") (pinfunction "2_2") (pintype "passive"))
      (node (ref "R48") (pin "2") (pinfunction "2_2") (pintype "passive"))
      (node (ref "U11") (pin "5") (pinfunction "VCC_5") (pintype "passive"))
      (node (ref "U15") (pin "4") (pinfunction "VCC_4") (pintype "passive"))
      (node (ref "U9") (pin "104") (pinfunction "VMV2_104") (pintype "passive"))
      (node (ref "U9") (pin "123") (pinfunction "VCCI_B1_123") (pintype "passive"))
      (node (ref "U9") (pin "140") (pinfunction "VCCI_B1_140") (pintype "passive"))
      (node (ref "U9") (pin "154") (pinfunction "VMV1_154") (pintype "passive"))
      (node (ref "U9") (pin "157") (pinfunction "VMV0_157") (pintype "passive"))
      (node (ref "U9") (pin "170") (pinfunction "VCCI_B0_170") (pintype "passive"))
      (node (ref "U9") (pin "18") (pinfunction "VCCI_B3_18") (pintype "passive"))
      (node (ref "U9") (pin "186") (pinfunction "VCCI_B0_186") (pintype "passive"))
      (node (ref "U9") (pin "200") (pinfunction "VCCI_B0_200") (pintype "passive"))
      (node (ref "U9") (pin "208") (pinfunction "VMV0_208") (pintype "passive"))
      (node (ref "U9") (pin "40") (pinfunction "VCCI_B3_40") (pintype "passive"))
      (node (ref "U9") (pin "50") (pinfunction "VMV3_50") (pintype "passive"))
      (node (ref "U9") (pin "53") (pinfunction "VMV2_53") (pintype "passive"))
      (node (ref "U9") (pin "62") (pinfunction "VCCI_B2_62") (pintype "passive"))
      (node (ref "U9") (pin "72") (pinfunction "VCCI_B2_72") (pintype "passive"))
      (node (ref "U9") (pin "89") (pinfunction "VCCI_B2_89") (pintype "passive"))
    )
    (net (code "105") (name "D_5V") (class "Default")
      (node (ref "C45") (pin "1") (pinfunction "1_1") (pintype "passive"))
      (node (ref "C46") (pin "1") (pinfunction "1_1") (pintype "passive"))
      (node (ref "C47") (pin "1") (pinfunction "1_1") (pintype "passive"))
      (node (ref "C60") (pin "2") (pinfunction "2_2") (pintype "passive"))
      (node (ref "C61") (pin "2") (pinfunction "2_2") (pintype "passive"))
      (node (ref "C62") (pin "2") (pinfunction "2_2") (pintype "passive"))
      (node (ref "C63") (pin "2") (pinfunction "2_2") (pintype "passive"))
      (node (ref "C64") (pin "2") (pinfunction "2_2") (pintype "passive"))
      (node (ref "D1") (pin "2") (pinfunction "2_2") (pintype "passive"))
      (node (ref "D3") (pin "2") (pinfunction "2_2") (pintype "passive"))
      (node (ref "D4") (pin "2") (pinfunction "2_2") (pintype "passive"))
      (node (ref "D6") (pin "2") (pinfunction "2_2") (pintype "passive"))
      (node (ref "D7") (pin "2") (pinfunction "2_2") (pintype "passive"))
      (node (ref "D9") (pin "2") (pinfunction "2_2") (pintype "passive"))
      (node (ref "R34") (pin "2") (pinfunction "2_2") (pintype "passive"))
      (node (ref "R39") (pin "2") (pinfunction "2_2") (pintype "passive"))
      (node (ref "T1") (pin "2") (pintype "passive"))
      (node (ref "T3") (pin "2") (pintype "passive"))
      (node (ref "T4") (pin "2") (pintype "passive"))
      (node (ref "U10") (pin "10") (pinfunction "2STROBE_10") (pintype "passive"))
      (node (ref "U10") (pin "14") (pinfunction "VCC_14") (pintype "passive"))
      (node (ref "U12") (pin "8") (pinfunction "VCC_8") (pintype "passive"))
      (node (ref "U13") (pin "8") (pinfunction "VCC_8") (pintype "passive"))
      (node (ref "U14") (pin "8") (pinfunction "VCC_8") (pintype "passive"))
    )
    (net (code "106") (name "Net-(D1-Pad3)") (class "Default")
      (node (ref "D1") (pin "3") (pinfunction "3_3") (pintype "passive"))
      (node (ref "D2") (pin "3") (pinfunction "3_3") (pintype "passive"))
      (node (ref "R41") (pin "2") (pinfunction "2_2") (pintype "passive"))
    )
    (net (code "107") (name "Net-(D2-Pad4)") (class "Default")
      (node (ref "D2") (pin "4") (pinfunction "4_4") (pintype "passive"))
      (node (ref "D3") (pin "3") (pinfunction "3_3") (pintype "passive"))
      (node (ref "R42") (pin "2") (pinfunction "2_2") (pintype "passive"))
    )
    (net (code "108") (name "Net-(D4-Pad3)") (class "Default")
      (node (ref "D4") (pin "3") (pinfunction "3_3") (pintype "passive"))
      (node (ref "D5") (pin "3") (pinfunction "3_3") (pintype "passive"))
      (node (ref "R43") (pin "1") (pinfunction "1_1") (pintype "passive"))
    )
    (net (code "109") (name "Net-(D5-Pad4)") (class "Default")
      (node (ref "D5") (pin "4") (pinfunction "4_4") (pintype "passive"))
      (node (ref "D6") (pin "3") (pinfunction "3_3") (pintype "passive"))
      (node (ref "R44") (pin "1") (pinfunction "1_1") (pintype "passive"))
    )
    (net (code "110") (name "Net-(D7-Pad3)") (class "Default")
      (node (ref "D7") (pin "3") (pinfunction "3_3") (pintype "passive"))
      (node (ref "D8") (pin "3") (pinfunction "3_3") (pintype "passive"))
      (node (ref "R45") (pin "1") (pinfunction "1_1") (pintype "passive"))
    )
    (net (code "111") (name "Net-(D8-Pad4)") (class "Default")
      (node (ref "D8") (pin "4") (pinfunction "4_4") (pintype "passive"))
      (node (ref "D9") (pin "3") (pinfunction "3_3") (pintype "passive"))
      (node (ref "R46") (pin "1") (pinfunction "1_1") (pintype "passive"))
    )
    (net (code "112") (name "Net-(T1-Pri+)") (class "Default")
      (node (ref "R41") (pin "1") (pinfunction "1_1") (pintype "passive"))
      (node (ref "T1") (pin "1") (pinfunction "Pri+_1") (pintype "passive"))
    )
    (net (code "113") (name "Net-(T1-Pri-)") (class "Default")
      (node (ref "R42") (pin "1") (pinfunction "1_1") (pintype "passive"))
      (node (ref "T1") (pin "3") (pinfunction "Pri-_3") (pintype "passive"))
    )
    (net (code "114") (name "Net-(T2-Sec+)") (class "Default")
      (node (ref "R36") (pin "2") (pinfunction "2_2") (pintype "passive"))
      (node (ref "R38") (pin "2") (pinfunction "2_2") (pintype "passive"))
      (node (ref "T2") (pin "7") (pinfunction "Sec+_7") (pintype "passive"))
    )
    (net (code "115") (name "Net-(T2-Sec-)") (class "Default")
      (node (ref "R35") (pin "1") (pinfunction "1_1") (pintype "passive"))
      (node (ref "R36") (pin "1") (pinfunction "1_1") (pintype "passive"))
      (node (ref "T2") (pin "5") (pinfunction "Sec-_5") (pintype "passive"))
    )
    (net (code "116") (name "Net-(T3-Pri+)") (class "Default")
      (node (ref "R43") (pin "2") (pinfunction "2_2") (pintype "passive"))
      (node (ref "T3") (pin "1") (pinfunction "Pri+_1") (pintype "passive"))
    )
    (net (code "117") (name "Net-(T3-Pri-)") (class "Default")
      (node (ref "R44") (pin "2") (pinfunction "2_2") (pintype "passive"))
      (node (ref "T3") (pin "3") (pinfunction "Pri-_3") (pintype "passive"))
    )
    (net (code "118") (name "Net-(T4-Pri+)") (class "Default")
      (node (ref "R45") (pin "2") (pinfunction "2_2") (pintype "passive"))
      (node (ref "T4") (pin "1") (pinfunction "Pri+_1") (pintype "passive"))
    )
    (net (code "119") (name "Net-(T4-Pri-)") (class "Default")
      (node (ref "R46") (pin "2") (pinfunction "2_2") (pintype "passive"))
      (node (ref "T4") (pin "3") (pinfunction "Pri-_3") (pintype "passive"))
    )
    (net (code "120") (name "Net-(U9A-VCCPLF)") (class "Default")
      (node (ref "C58") (pin "2") (pinfunction "2_2") (pintype "passive"))
      (node (ref "C59") (pin "2") (pinfunction "2_2") (pintype "passive"))
      (node (ref "FB1") (pin "2") (pinfunction "2_2") (pintype "passive"))
      (node (ref "U9") (pin "27") (pinfunction "VCCPLF_27") (pintype "passive"))
    )
    (net (code "121") (name "Net-(U9A-VCOMPLF)") (class "Default")
      (node (ref "C58") (pin "1") (pinfunction "1_1") (pintype "passive"))
      (node (ref "C59") (pin "1") (pinfunction "1_1") (pintype "passive"))
      (node (ref "FB2") (pin "2") (pinfunction "2_2") (pintype "passive"))
      (node (ref "U9") (pin "25") (pinfunction "VCOMPLF_25") (pintype "passive"))
    )
    (net (code "122") (name "Net-(U9C-GCA0{slash}IO93NDB1)") (class "Default")
      (node (ref "DCKL1") (pin "1") (pinfunction "1_1") (pintype "passive"))
      (node (ref "U9") (pin "133") (pinfunction "GCA0/IO93NDB1_133") (pintype "passive"))
    )
    (net (code "123") (name "Net-(U9C-GCA1{slash}IO93PDB1)") (class "Default")
      (node (ref "MODE1") (pin "1") (pinfunction "1_1") (pintype "passive"))
      (node (ref "U9") (pin "132") (pinfunction "GCA1/IO93PDB1_132") (pintype "passive"))
    )
    (net (code "124") (name "Net-(U9C-GCA2{slash}IO94PSB1)") (class "Default")
      (node (ref "MODE0") (pin "1") (pinfunction "1_1") (pintype "passive"))
      (node (ref "U9") (pin "131") (pinfunction "GCA2/IO94PSB1_131") (pintype "passive"))
    )
    (net (code "125") (name "Net-(U9C-GCB0{slash}IO92NDB1)") (class "Default")
      (node (ref "ECLK3") (pin "1") (pinfunction "1_1") (pintype "passive"))
      (node (ref "U9") (pin "134") (pinfunction "GCB0/IO92NDB1_134") (pintype "passive"))
    )
    (net (code "126") (name "Net-(U9C-GCB1{slash}IO92PDB1)") (class "Default")
      (node (ref "FLAG2") (pin "1") (pinfunction "1_1") (pintype "passive"))
      (node (ref "U9") (pin "135") (pinfunction "GCB1/IO92PDB1_135") (pintype "passive"))
    )
    (net (code "127") (name "Net-(U9C-GCB2{slash}IO95PSB1)") (class "Default")
      (node (ref "ECLK2") (pin "1") (pinfunction "1_1") (pintype "passive"))
      (node (ref "U9") (pin "129") (pinfunction "GCB2/IO95PSB1_129") (pintype "passive"))
    )
    (net (code "128") (name "Net-(U9C-GCC0{slash}IO91NDB1)") (class "Default")
      (node (ref "FLAG3") (pin "1") (pinfunction "1_1") (pintype "passive"))
      (node (ref "U9") (pin "136") (pinfunction "GCC0/IO91NDB1_136") (pintype "passive"))
    )
    (net (code "129") (name "Net-(U9C-GCC2{slash}IO96PDB1)") (class "Default")
      (node (ref "ECLK1") (pin "1") (pinfunction "1_1") (pintype "passive"))
      (node (ref "U9") (pin "128") (pinfunction "GCC2/IO96PDB1_128") (pintype "passive"))
    )
    (net (code "130") (name "Net-(U9C-IO96NDB1)") (class "Default")
      (node (ref "FLAG1") (pin "1") (pinfunction "1_1") (pintype "passive"))
      (node (ref "U9") (pin "127") (pinfunction "IO96NDB1_127") (pintype "passive"))
    )
    (net (code "131") (name "Net-(U9D-IO197PSB3)") (class "Default")
      (node (ref "TST_S4") (pin "1") (pinfunction "1_1") (pintype "passive"))
      (node (ref "U9") (pin "39") (pinfunction "IO197PSB3_39") (pintype "passive"))
    )
    (net (code "132") (name "Net-(U9D-IO199NDB3)") (class "Default")
      (node (ref "TST_S3") (pin "1") (pinfunction "1_1") (pintype "passive"))
      (node (ref "U9") (pin "38") (pinfunction "IO199NDB3_38") (pintype "passive"))
    )
    (net (code "133") (name "Net-(U9D-IO199PDB3)") (class "Default")
      (node (ref "TST_S2") (pin "1") (pinfunction "1_1") (pintype "passive"))
      (node (ref "U9") (pin "37") (pinfunction "IO199PDB3_37") (pintype "passive"))
    )
    (net (code "134") (name "Net-(U9D-IO204NDB3)") (class "Default")
      (node (ref "TST_S1") (pin "1") (pinfunction "1_1") (pintype "passive"))
      (node (ref "U9") (pin "35") (pinfunction "IO204NDB3_35") (pintype "passive"))
    )
    (net (code "135") (name "Net-(U10-2IN+)") (class "Default")
      (node (ref "R37") (pin "2") (pinfunction "2_2") (pintype "passive"))
      (node (ref "R38") (pin "1") (pinfunction "1_1") (pintype "passive"))
      (node (ref "U10") (pin "11") (pinfunction "2IN+_11") (pintype "passive"))
    )
    (net (code "136") (name "Net-(U10-2IN-)") (class "Default")
      (node (ref "R34") (pin "1") (pinfunction "1_1") (pintype "passive"))
      (node (ref "R35") (pin "2") (pinfunction "2_2") (pintype "passive"))
      (node (ref "U10") (pin "13") (pinfunction "2IN-_13") (pintype "passive"))
    )
    (net (code "137") (name "Net-(U12-1Y)") (class "Default")
      (node (ref "D2") (pin "1") (pinfunction "1_1") (pintype "passive"))
      (node (ref "U12") (pin "3") (pinfunction "1Y_3") (pintype "passive"))
    )
    (net (code "138") (name "Net-(U12-2Y)") (class "Default")
      (node (ref "D2") (pin "2") (pinfunction "2_2") (pintype "passive"))
      (node (ref "U12") (pin "5") (pinfunction "2Y_5") (pintype "passive"))
    )
    (net (code "139") (name "Net-(U13-1Y)") (class "Default")
      (node (ref "D5") (pin "1") (pinfunction "1_1") (pintype "passive"))
      (node (ref "U13") (pin "3") (pinfunction "1Y_3") (pintype "passive"))
    )
    (net (code "140") (name "Net-(U13-2Y)") (class "Default")
      (node (ref "D5") (pin "2") (pinfunction "2_2") (pintype "passive"))
      (node (ref "U13") (pin "5") (pinfunction "2Y_5") (pintype "passive"))
    )
    (net (code "141") (name "Net-(U14-1Y)") (class "Default")
      (node (ref "D8") (pin "1") (pinfunction "1_1") (pintype "passive"))
      (node (ref "U14") (pin "3") (pinfunction "1Y_3") (pintype "passive"))
    )
    (net (code "142") (name "Net-(U14-2Y)") (class "Default")
      (node (ref "D8") (pin "2") (pinfunction "2_2") (pintype "passive"))
      (node (ref "U14") (pin "5") (pinfunction "2Y_5") (pintype "passive"))
    )
    (net (code "143") (name "unconnected-(P2-Pad4)") (class "Default")
      (node (ref "P2") (pin "4") (pinfunction "4_4") (pintype "passive+no_connect"))
    )
    (net (code "144") (name "unconnected-(T1-SecCT-Pad6)") (class "Default")
      (node (ref "T1") (pin "6") (pinfunction "SecCT_6") (pintype "passive+no_connect"))
    )
    (net (code "145") (name "unconnected-(T2-Pad2)") (class "Default")
      (node (ref "T2") (pin "2") (pintype "passive+no_connect"))
    )
    (net (code "146") (name "unconnected-(T2-SecCT-Pad6)") (class "Default")
      (node (ref "T2") (pin "6") (pinfunction "SecCT_6") (pintype "passive+no_connect"))
    )
    (net (code "147") (name "unconnected-(T3-SecCT-Pad6)") (class "Default")
      (node (ref "T3") (pin "6") (pinfunction "SecCT_6") (pintype "passive+no_connect"))
    )
    (net (code "148") (name "unconnected-(T4-SecCT-Pad6)") (class "Default")
      (node (ref "T4") (pin "6") (pinfunction "SecCT_6") (pintype "passive+no_connect"))
    )
    (net (code "149") (name "unconnected-(U9C-GAA0{slash}IO00RSB0-Pad206)") (class "Default")
      (node (ref "U9") (pin "206") (pinfunction "GAA0/IO00RSB0_206") (pintype "passive+no_connect"))
    )
    (net (code "150") (name "unconnected-(U9C-GAA1{slash}IO01RSB0-Pad205)") (class "Default")
      (node (ref "U9") (pin "205") (pinfunction "GAA1/IO01RSB0_205") (pintype "passive+no_connect"))
    )
    (net (code "151") (name "unconnected-(U9C-GCC1{slash}IO91PDB1-Pad137)") (class "Default")
      (node (ref "U9") (pin "137") (pinfunction "GCC1/IO91PDB1_137") (pintype "passive+no_connect"))
    )
    (net (code "152") (name "unconnected-(U9C-IO12RSB0-Pad196)") (class "Default")
      (node (ref "U9") (pin "196") (pinfunction "IO12RSB0_196") (pintype "passive"))
    )
    (net (code "153") (name "unconnected-(U9C-IO67RSB0-Pad166)") (class "Default")
      (node (ref "U9") (pin "166") (pinfunction "IO67RSB0_166") (pintype "passive"))
    )
    (net (code "154") (name "unconnected-(U9C-IO79NDB1-Pad150)") (class "Default")
      (node (ref "U9") (pin "150") (pinfunction "IO79NDB1_150") (pintype "passive+no_connect"))
    )
    (net (code "155") (name "unconnected-(U9C-IO80NDB1-Pad148)") (class "Default")
      (node (ref "U9") (pin "148") (pinfunction "IO80NDB1_148") (pintype "passive+no_connect"))
    )
    (net (code "156") (name "unconnected-(U9C-IO82NDB1-Pad146)") (class "Default")
      (node (ref "U9") (pin "146") (pinfunction "IO82NDB1_146") (pintype "passive+no_connect"))
    )
    (net (code "157") (name "unconnected-(U9C-IO84NDB1-Pad144)") (class "Default")
      (node (ref "U9") (pin "144") (pinfunction "IO84NDB1_144") (pintype "passive+no_connect"))
    )
    (net (code "158") (name "unconnected-(U9C-IO84PDB1-Pad145)") (class "Default")
      (node (ref "U9") (pin "145") (pinfunction "IO84PDB1_145") (pintype "passive+no_connect"))
    )
    (net (code "159") (name "unconnected-(U9C-IO86PSB1-Pad143)") (class "Default")
      (node (ref "U9") (pin "143") (pinfunction "IO86PSB1_143") (pintype "passive+no_connect"))
    )
    (net (code "160") (name "unconnected-(U9C-IO88NDB1-Pad138)") (class "Default")
      (node (ref "U9") (pin "138") (pinfunction "IO88NDB1_138") (pintype "passive+no_connect"))
    )
    (net (code "161") (name "unconnected-(U9C-IO88PDB1-Pad139)") (class "Default")
      (node (ref "U9") (pin "139") (pinfunction "IO88PDB1_139") (pintype "passive+no_connect"))
    )
    (net (code "162") (name "unconnected-(U9C-IO99NDB1-Pad124)") (class "Default")
      (node (ref "U9") (pin "124") (pinfunction "IO99NDB1_124") (pintype "passive+no_connect"))
    )
    (net (code "163") (name "unconnected-(U9C-IO99PDB1-Pad125)") (class "Default")
      (node (ref "U9") (pin "125") (pinfunction "IO99PDB1_125") (pintype "passive+no_connect"))
    )
    (net (code "164") (name "unconnected-(U9C-IO104PSB1-Pad121)") (class "Default")
      (node (ref "U9") (pin "121") (pinfunction "IO104PSB1_121") (pintype "passive+no_connect"))
    )
    (net (code "165") (name "unconnected-(U9C-IO106NDB1-Pad119)") (class "Default")
      (node (ref "U9") (pin "119") (pinfunction "IO106NDB1_119") (pintype "passive+no_connect"))
    )
    (net (code "166") (name "unconnected-(U9C-IO106PDB1-Pad120)") (class "Default")
      (node (ref "U9") (pin "120") (pinfunction "IO106PDB1_120") (pintype "passive+no_connect"))
    )
    (net (code "167") (name "unconnected-(U9C-IO109NDB1-Pad117)") (class "Default")
      (node (ref "U9") (pin "117") (pinfunction "IO109NDB1_117") (pintype "passive+no_connect"))
    )
    (net (code "168") (name "unconnected-(U9C-IO109PDB1-Pad118)") (class "Default")
      (node (ref "U9") (pin "118") (pinfunction "IO109PDB1_118") (pintype "passive+no_connect"))
    )
    (net (code "169") (name "unconnected-(U9D-GAC2{slash}IO223PDB3-Pad6)") (class "Default")
      (node (ref "U9") (pin "6") (pinfunction "GAC2/IO223PDB3_6") (pintype "passive+no_connect"))
    )
    (net (code "170") (name "unconnected-(U9D-GEA0{slash}IO188NDB3-Pad49)") (class "Default")
      (node (ref "U9") (pin "49") (pinfunction "GEA0/IO188NDB3_49") (pintype "passive+no_connect"))
    )
    (net (code "171") (name "unconnected-(U9D-GFA0{slash}IO207NDB3-Pad26)") (class "Default")
      (node (ref "U9") (pin "26") (pinfunction "GFA0/IO207NDB3_26") (pintype "passive+no_connect"))
    )
    (net (code "172") (name "unconnected-(U9D-GFA1{slash}IO207PDB3-Pad28)") (class "Default")
      (node (ref "U9") (pin "28") (pinfunction "GFA1/IO207PDB3_28") (pintype "passive+no_connect"))
    )
    (net (code "173") (name "unconnected-(U9D-GFA2{slash}IO206PDB3-Pad30)") (class "Default")
      (node (ref "U9") (pin "30") (pinfunction "GFA2/IO206PDB3_30") (pintype "passive+no_connect"))
    )
    (net (code "174") (name "unconnected-(U9D-GFB2{slash}IO205PDB3-Pad32)") (class "Default")
      (node (ref "U9") (pin "32") (pinfunction "GFB2/IO205PDB3_32") (pintype "passive+no_connect"))
    )
    (net (code "175") (name "unconnected-(U9D-GFC2{slash}IO204PDB3-Pad34)") (class "Default")
      (node (ref "U9") (pin "34") (pinfunction "GFC2/IO204PDB3_34") (pintype "passive+no_connect"))
    )
    (net (code "176") (name "unconnected-(U9D-IO135RSB2-Pad86)") (class "Default")
      (node (ref "U9") (pin "86") (pinfunction "IO135RSB2_86") (pintype "passive+no_connect"))
    )
    (net (code "177") (name "unconnected-(U9D-IO137RSB2-Pad85)") (class "Default")
      (node (ref "U9") (pin "85") (pinfunction "IO137RSB2_85") (pintype "passive+no_connect"))
    )
    (net (code "178") (name "unconnected-(U9D-IO139RSB2-Pad84)") (class "Default")
      (node (ref "U9") (pin "84") (pinfunction "IO139RSB2_84") (pintype "passive+no_connect"))
    )
    (net (code "179") (name "unconnected-(U9D-IO148RSB2-Pad80)") (class "Default")
      (node (ref "U9") (pin "80") (pinfunction "IO148RSB2_80") (pintype "passive"))
    )
    (net (code "180") (name "unconnected-(U9D-IO152RSB2-Pad78)") (class "Default")
      (node (ref "U9") (pin "78") (pinfunction "IO152RSB2_78") (pintype "passive"))
    )
    (net (code "181") (name "unconnected-(U9D-IO154RSB2-Pad77)") (class "Default")
      (node (ref "U9") (pin "77") (pinfunction "IO154RSB2_77") (pintype "passive"))
    )
    (net (code "182") (name "unconnected-(U9D-IO156RSB2-Pad76)") (class "Default")
      (node (ref "U9") (pin "76") (pinfunction "IO156RSB2_76") (pintype "passive"))
    )
    (net (code "183") (name "unconnected-(U9D-IO158RSB2-Pad75)") (class "Default")
      (node (ref "U9") (pin "75") (pinfunction "IO158RSB2_75") (pintype "passive"))
    )
    (net (code "184") (name "unconnected-(U9D-IO174RSB2-Pad66)") (class "Default")
      (node (ref "U9") (pin "66") (pinfunction "IO174RSB2_66") (pintype "passive+no_connect"))
    )
    (net (code "185") (name "unconnected-(U9D-IO176RSB2-Pad64)") (class "Default")
      (node (ref "U9") (pin "64") (pinfunction "IO176RSB2_64") (pintype "passive"))
    )
    (net (code "186") (name "unconnected-(U9D-IO178RSB2-Pad63)") (class "Default")
      (node (ref "U9") (pin "63") (pinfunction "IO178RSB2_63") (pintype "passive"))
    )
    (net (code "187") (name "unconnected-(U9D-IO180RSB2-Pad61)") (class "Default")
      (node (ref "U9") (pin "61") (pinfunction "IO180RSB2_61") (pintype "passive"))
    )
    (net (code "188") (name "unconnected-(U9D-IO181RSB2-Pad60)") (class "Default")
      (node (ref "U9") (pin "60") (pinfunction "IO181RSB2_60") (pintype "passive"))
    )
    (net (code "189") (name "unconnected-(U9D-IO182RSB2-Pad59)") (class "Default")
      (node (ref "U9") (pin "59") (pinfunction "IO182RSB2_59") (pintype "passive"))
    )
    (net (code "190") (name "unconnected-(U9D-IO183RSB2-Pad58)") (class "Default")
      (node (ref "U9") (pin "58") (pinfunction "IO183RSB2_58") (pintype "passive"))
    )
    (net (code "191") (name "unconnected-(U9D-IO184RSB2-Pad57)") (class "Default")
      (node (ref "U9") (pin "57") (pinfunction "IO184RSB2_57") (pintype "passive"))
    )
    (net (code "192") (name "unconnected-(U9D-IO191NDB3-Pad43)") (class "Default")
      (node (ref "U9") (pin "43") (pinfunction "IO191NDB3_43") (pintype "passive"))
    )
    (net (code "193") (name "unconnected-(U9D-IO191PDB3-Pad42)") (class "Default")
      (node (ref "U9") (pin "42") (pinfunction "IO191PDB3_42") (pintype "passive+no_connect"))
    )
    (net (code "194") (name "unconnected-(U9D-IO205NDB3-Pad33)") (class "Default")
      (node (ref "U9") (pin "33") (pinfunction "IO205NDB3_33") (pintype "passive+no_connect"))
    )
    (net (code "195") (name "unconnected-(U9D-IO206NDB3-Pad31)") (class "Default")
      (node (ref "U9") (pin "31") (pinfunction "IO206NDB3_31") (pintype "passive+no_connect"))
    )
    (net (code "196") (name "unconnected-(U9D-IO212PDB3-Pad19)") (class "Default")
      (node (ref "U9") (pin "19") (pinfunction "IO212PDB3_19") (pintype "passive+no_connect"))
    )
    (net (code "197") (name "unconnected-(U9D-IO216NDB3-Pad15)") (class "Default")
      (node (ref "U9") (pin "15") (pinfunction "IO216NDB3_15") (pintype "passive+no_connect"))
    )
    (net (code "198") (name "unconnected-(U9D-IO216PDB3-Pad14)") (class "Default")
      (node (ref "U9") (pin "14") (pinfunction "IO216PDB3_14") (pintype "passive+no_connect"))
    )
    (net (code "199") (name "unconnected-(U9D-IO218NDB3-Pad13)") (class "Default")
      (node (ref "U9") (pin "13") (pinfunction "IO218NDB3_13") (pintype "passive+no_connect"))
    )
    (net (code "200") (name "unconnected-(U9D-IO218PDB3-Pad12)") (class "Default")
      (node (ref "U9") (pin "12") (pinfunction "IO218PDB3_12") (pintype "passive+no_connect"))
    )
    (net (code "201") (name "unconnected-(U9D-IO220NDB3-Pad11)") (class "Default")
      (node (ref "U9") (pin "11") (pinfunction "IO220NDB3_11") (pintype "passive+no_connect"))
    )
    (net (code "202") (name "unconnected-(U9D-IO220PDB3-Pad10)") (class "Default")
      (node (ref "U9") (pin "10") (pinfunction "IO220PDB3_10") (pintype "passive+no_connect"))
    )
    (net (code "203") (name "unconnected-(U9D-IO222NDB3-Pad9)") (class "Default")
      (node (ref "U9") (pin "9") (pinfunction "IO222NDB3_9") (pintype "passive+no_connect"))
    )
    (net (code "204") (name "unconnected-(U9D-IO222PDB3-Pad8)") (class "Default")
      (node (ref "U9") (pin "8") (pinfunction "IO222PDB3_8") (pintype "passive+no_connect"))
    )
    (net (code "205") (name "unconnected-(U9D-IO223NDB3-Pad7)") (class "Default")
      (node (ref "U9") (pin "7") (pinfunction "IO223NDB3_7") (pintype "passive+no_connect"))
    )
    (net (code "206") (name "unconnected-(U9D-IO224NDB3-Pad5)") (class "Default")
      (node (ref "U9") (pin "5") (pinfunction "IO224NDB3_5") (pintype "passive+no_connect"))
    )
    (net (code "207") (name "unconnected-(U10-1IN+-Pad3)") (class "Default")
      (node (ref "U10") (pin "3") (pinfunction "1IN+_3") (pintype "passive+no_connect"))
    )
    (net (code "208") (name "unconnected-(U10-1IN--Pad1)") (class "Default")
      (node (ref "U10") (pin "1") (pinfunction "1IN-_1") (pintype "passive+no_connect"))
    )
    (net (code "209") (name "unconnected-(U10-1OUT-Pad6)") (class "Default")
      (node (ref "U10") (pin "6") (pinfunction "1OUT_6") (pintype "passive+no_connect"))
    )
    (net (code "210") (name "unconnected-(U10-1RESP-Pad5)") (class "Default")
      (node (ref "U10") (pin "5") (pinfunction "1RESP_5") (pintype "passive+no_connect"))
    )
    (net (code "211") (name "unconnected-(U10-1STROBE-Pad4)") (class "Default")
      (node (ref "U10") (pin "4") (pinfunction "1STROBE_4") (pintype "passive+no_connect"))
    )
    (net (code "212") (name "unconnected-(U10-1TERMI--Pad2)") (class "Default")
      (node (ref "U10") (pin "2") (pinfunction "1TERMI-_2") (pintype "passive+no_connect"))
    )
    (net (code "213") (name "unconnected-(U10-2RESP-Pad9)") (class "Default")
      (node (ref "U10") (pin "9") (pinfunction "2RESP_9") (pintype "passive+no_connect"))
    )
    (net (code "214") (name "unconnected-(U10-2TERMI-Pad12)") (class "Default")
      (node (ref "U10") (pin "12") (pinfunction "2TERMI_12") (pintype "passive+no_connect"))
    )
    (net (code "215") (name "unconnected-(U11-NC-Pad1)") (class "Default")
      (node (ref "U11") (pin "1") (pinfunction "NC_1") (pintype "passive"))
    )
    (net (code "216") (name "unconnected-(U15-NC-Pad1)") (class "Default")
      (node (ref "U15") (pin "1") (pinfunction "NC_1") (pintype "passive+no_connect"))
    )
  )
)
